# 10_MT7688AN_USB-PCIe.net
KiCad netlist of a schematic drawn in Altium Designer
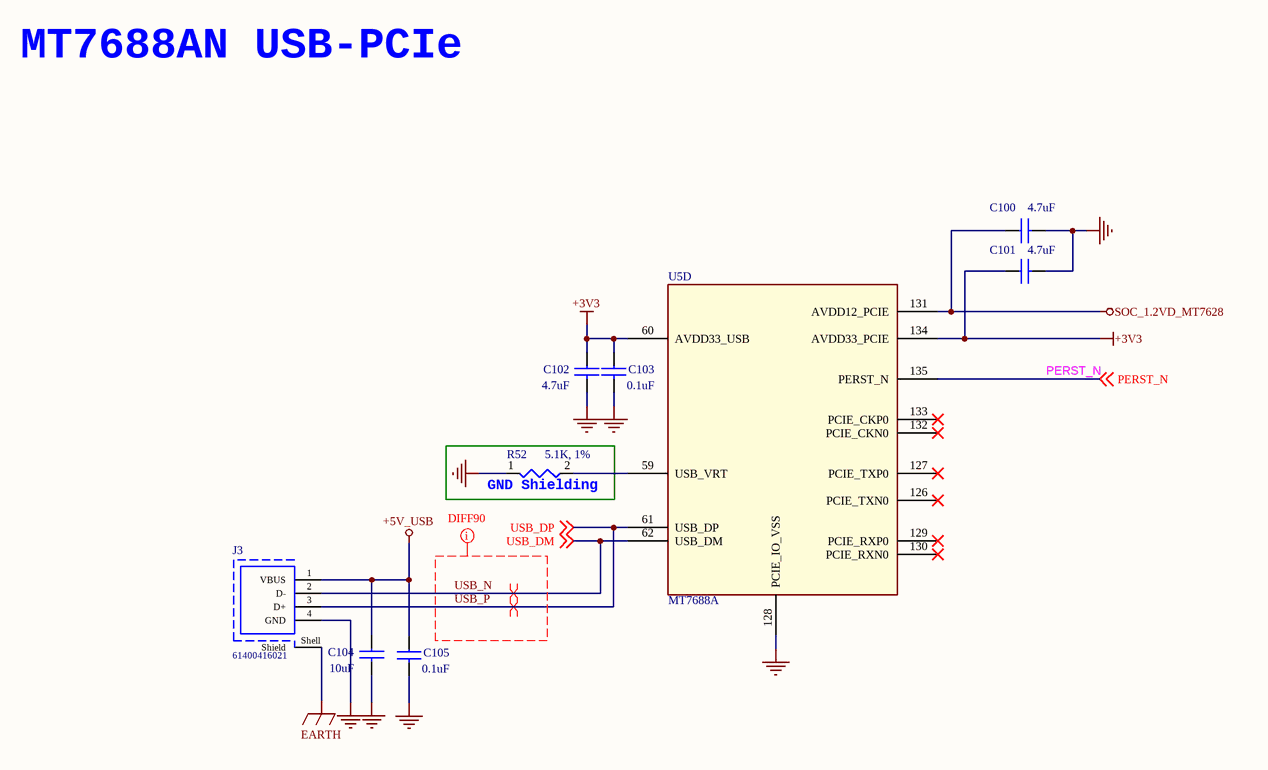
[diagram p0: 10. MT7688AN USB-PCIe.SchDoc]

(export (version "E")
  (design (tool "Eeschema 10.0.6"))
  (components
    (comp (ref "C100")
      (value "4.7uF")
      (footprint "CAPC1005X60X30LL05T10 - duplicate")
      (libsource (lib "MT7688AN") (part "CAP NP"))
    )
    (comp (ref "C101")
      (value "4.7uF")
      (footprint "CAPC1005X60X30LL05T10 - duplicate")
      (libsource (lib "MT7688AN") (part "CAP NP"))
    )
    (comp (ref "C102")
      (value "4.7uF")
      (footprint "CAPC1005X60X30NL05T10")
      (libsource (lib "MT7688AN") (part "CAP NP"))
    )
    (comp (ref "C103")
      (value "0.1uF")
      (footprint "CAPC1005X60X30NL05T10")
      (libsource (lib "MT7688AN") (part "CAP NP"))
    )
    (comp (ref "C104")
      (value "10uF")
      (footprint "CAPC1608X90X35NL10T15")
      (libsource (lib "MT7688AN") (part "CAP NP"))
    )
    (comp (ref "C105")
      (value "0.1uF")
      (footprint "CAPC1005X60X30LL05T10 - duplicate")
      (libsource (lib "MT7688AN") (part "CAP NP"))
    )
    (comp (ref "J3")
      (value "61400416021")
      (footprint "61400416021")
      (description "USB 2.0 Type A Receptacle WR-COM, Horizontal, THT")
      (fields (field (name "MANUFACTURER") "Wurth Elektronik") (field (name "PUBLISHER") "WurthElektronik"))
      (libsource (lib "Altium Content Vault") (part "WE-USB-4-1SHLD"))
    )
    (comp (ref "R52")
      (value "5.1K, 1%")
      (footprint "RESC1005X40X25NL05T10 - duplicate")
      (libsource (lib "MT7688AN") (part "RES/0402_3"))
    )
    (comp (ref "U5")
      (value "MT7688A")
      (footprint "MT7628AN$2F$DRQFN156$2F$SMD$2F$P0.5$2F$12X12")
      (libsource (lib "MT7688AN") (part "MT7620N-n_26"))
    )
  )
  (nets
    (net (code "1") (name "+3V3") (class "Default")
      (node (ref "C101") (pin "1") (pinfunction "1_1") (pintype "passive"))
      (node (ref "C102") (pin "1") (pinfunction "1_1") (pintype "passive"))
      (node (ref "C103") (pin "1") (pinfunction "1_1") (pintype "passive"))
      (node (ref "U5") (pin "134") (pinfunction "AVDD33_PCIE_134") (pintype "power_in"))
      (node (ref "U5") (pin "60") (pinfunction "AVDD33_USB_60") (pintype "passive"))
    )
    (net (code "2") (name "+5V_USB") (class "Default")
      (node (ref "C104") (pin "1") (pinfunction "1_1") (pintype "passive"))
      (node (ref "C105") (pin "1") (pinfunction "1_1") (pintype "passive"))
      (node (ref "J3") (pin "1") (pinfunction "VBUS_1") (pintype "passive"))
    )
    (net (code "3") (name "EARTH") (class "Default")
      (node (ref "J3") (pin "Shell") (pinfunction "Shield_Shell") (pintype "passive"))
    )
    (net (code "4") (name "GND") (class "Default")
      (node (ref "C100") (pin "2") (pinfunction "2_2") (pintype "passive"))
      (node (ref "C101") (pin "2") (pinfunction "2_2") (pintype "passive"))
      (node (ref "C102") (pin "2") (pinfunction "2_2") (pintype "passive"))
      (node (ref "C103") (pin "2") (pinfunction "2_2") (pintype "passive"))
      (node (ref "C104") (pin "2") (pinfunction "2_2") (pintype "passive"))
      (node (ref "C105") (pin "2") (pinfunction "2_2") (pintype "passive"))
      (node (ref "J3") (pin "4") (pinfunction "GND_4") (pintype "passive"))
      (node (ref "R52") (pin "1") (pinfunction "1_1") (pintype "passive"))
      (node (ref "U5") (pin "128") (pinfunction "PCIE_IO_VSS_128") (pintype "passive"))
    )
    (net (code "5") (name "Net-(U5D-USB_VRT)") (class "Default")
      (node (ref "R52") (pin "2") (pinfunction "2_2") (pintype "passive"))
      (node (ref "U5") (pin "59") (pinfunction "USB_VRT_59") (pintype "passive"))
    )
    (net (code "6") (name "PERST_N") (class "Default")
      (node (ref "U5") (pin "135") (pinfunction "PERST_N_135") (pintype "passive"))
    )
    (net (code "7") (name "SOC_1.2VD_MT7628") (class "Default")
      (node (ref "C100") (pin "1") (pinfunction "1_1") (pintype "passive"))
      (node (ref "U5") (pin "131") (pinfunction "AVDD12_PCIE_131") (pintype "power_in"))
    )
    (net (code "8") (name "USB_DM") (class "Default")
      (node (ref "J3") (pin "2") (pinfunction "D-_2") (pintype "passive"))
      (node (ref "U5") (pin "62") (pinfunction "USB_DM_62") (pintype "passive"))
    )
    (net (code "9") (name "USB_DP") (class "Default")
      (node (ref "J3") (pin "3") (pinfunction "D+_3") (pintype "passive"))
      (node (ref "U5") (pin "61") (pinfunction "USB_DP_61") (pintype "passive"))
    )
    (net (code "10") (name "unconnected-(U5D-PCIE_CKN0-Pad132)") (class "Default")
      (node (ref "U5") (pin "132") (pinfunction "PCIE_CKN0_132") (pintype "passive+no_connect"))
    )
    (net (code "11") (name "unconnected-(U5D-PCIE_CKP0-Pad133)") (class "Default")
      (node (ref "U5") (pin "133") (pinfunction "PCIE_CKP0_133") (pintype "passive+no_connect"))
    )
    (net (code "12") (name "unconnected-(U5D-PCIE_RXN0-Pad130)") (class "Default")
      (node (ref "U5") (pin "130") (pinfunction "PCIE_RXN0_130") (pintype "passive+no_connect"))
    )
    (net (code "13") (name "unconnected-(U5D-PCIE_RXP0-Pad129)") (class "Default")
      (node (ref "U5") (pin "129") (pinfunction "PCIE_RXP0_129") (pintype "passive+no_connect"))
    )
    (net (code "14") (name "unconnected-(U5D-PCIE_TXN0-Pad126)") (class "Default")
      (node (ref "U5") (pin "126") (pinfunction "PCIE_TXN0_126") (pintype "passive+no_connect"))
    )
    (net (code "15") (name "unconnected-(U5D-PCIE_TXP0-Pad127)") (class "Default")
      (node (ref "U5") (pin "127") (pinfunction "PCIE_TXP0_127") (pintype "passive+no_connect"))
    )
  )
)
